# main.net
KiCad netlist of a schematic drawn in Altium Designer
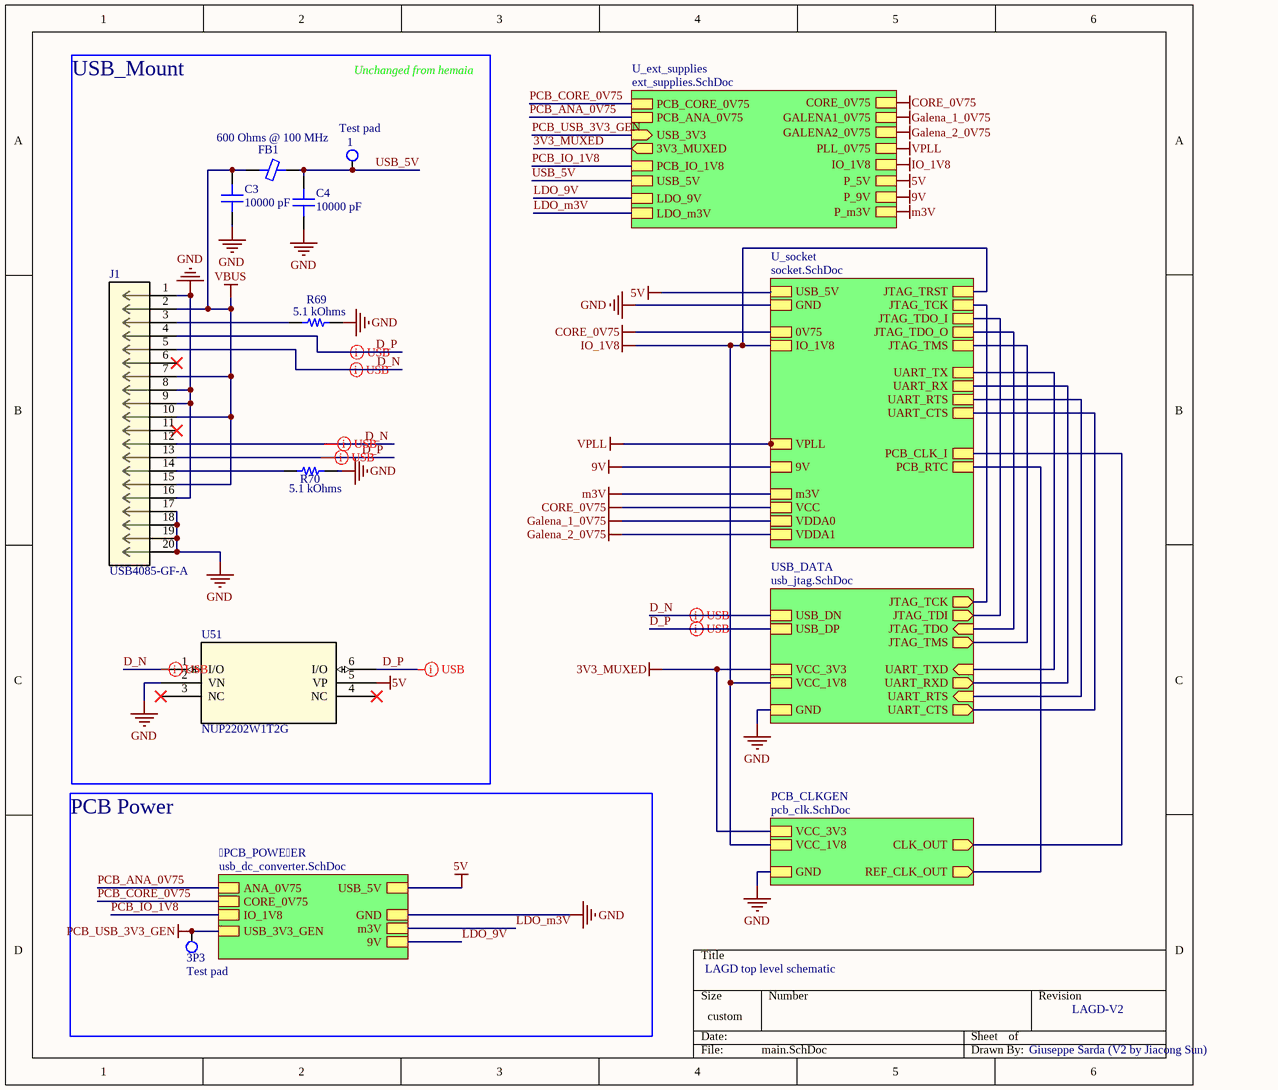
[diagram p0: main.SchDoc]

(export (version "E")
  (design (tool "Eeschema 10.0.6"))
  (components
    (comp (ref "1") (value "Test pad") (footprint "Test Pad") (libsource (lib "Hemaia") (part "Test pad")))
    (comp (ref "3P3") (value "Test pad") (footprint "Test Pad") (libsource (lib "Hemaia") (part "Test pad")))
    (comp (ref "C3")
      (value "10000 pF")
      (footprint "CAP 0805_2012")
      (description "CAP CER 0805 10NF 25V C0G 1%")
      (fields
        (field (name "PART NUMBER") "C0805C103F3GECTU")
        (field (name "CAPACITANCE") "10000 pF")
        (field (name "MANUFACTURER") "KEMET")
      )
      (libsource (lib "Celestial Altium Library - altium_library") (part "Capacitor"))
    )
    (comp (ref "C4")
      (value "10000 pF")
      (footprint "CAP 0805_2012")
      (description "CAP CER 0805 10NF 25V C0G 1%")
      (fields
        (field (name "PART NUMBER") "C0805C103F3GECTU")
        (field (name "CAPACITANCE") "10000 pF")
        (field (name "MANUFACTURER") "KEMET")
      )
      (libsource (lib "Celestial Altium Library - altium_library") (part "Capacitor"))
    )
    (comp (ref "FB1")
      (value "600 Ohms @ 100 MHz")
      (footprint "FER 0805_2012")
      (description "FERRITE BEAD 600 OHM 0805 1LN")
      (fields
        (field (name "PART NUMBER") "BLM21HE601SH1L")
        (field (name "MANUFACTURER") "Murata Electronics")
      )
      (libsource (lib "Celestial Altium Library - altium_library") (part "Ferrite Chip"))
    )
    (comp (ref "J1")
      (value "USB4085-GF-A")
      (footprint "FP-USB4085-GF-A-MFG")
      (description "Description")
      (fields (field (name "COPYRIGHT") "Copyright (C) 2025 Ultra Librarian. All rights reserved."))
      (libsource (lib "Connectors") (part "USB4085-GF-A"))
    )
    (comp (ref "R69")
      (value "5.1 kOhms")
      (footprint "RES 0805_2012")
      (description "RES 5.1K OHM 5% 1/4W 0805")
      (fields (field (name "PART NUMBER") "560112120019") (field (name "MANUFACTURER") "Würth Elektronik"))
      (libsource (lib "Celestial Altium Library - altium_library") (part "Resistor"))
    )
    (comp (ref "R70")
      (value "5.1 kOhms")
      (footprint "RES 0805_2012")
      (description "RES 5.1K OHM 5% 1/4W 0805")
      (fields (field (name "PART NUMBER") "560112120019") (field (name "MANUFACTURER") "Würth Elektronik"))
      (libsource (lib "Celestial Altium Library - altium_library") (part "Resistor"))
    )
    (comp (ref "U51")
      (value "NUP2202W1T2G")
      (footprint "SOT-363-6_2P2X1P35_ONS")
      (description "Description")
      (fields (field (name "COPYRIGHT") "Copyright (C) 2025 Ultra Librarian. All rights reserved."))
      (libsource (lib "Diodes") (part "NUP2202W1T2G"))
    )
  )
  (nets
    (net (code "2") (name "/D_N") (class "Default")
      (node (ref "J1") (pin "12") (pinfunction "12_12") (pintype "passive"))
      (node (ref "J1") (pin "5") (pinfunction "5_5") (pintype "passive"))
      (node (ref "U51") (pin "1") (pinfunction "I/O_1") (pintype "bidirectional"))
    )
    (net (code "3") (name "/D_P") (class "Default")
      (node (ref "J1") (pin "13") (pinfunction "13_13") (pintype "passive"))
      (node (ref "J1") (pin "4") (pinfunction "4_4") (pintype "passive"))
      (node (ref "U51") (pin "6") (pinfunction "I/O_6") (pintype "bidirectional"))
    )
    (net (code "18") (name "/USB_5V") (class "Default")
      (node (ref "1") (pin "1") (pintype "passive"))
      (node (ref "C4") (pin "1") (pinfunction "1_1") (pintype "passive"))
      (node (ref "FB1") (pin "2") (pinfunction "2_2") (pintype "passive"))
    )
    (net (code "20") (name "5V") (class "Default")
      (node (ref "U51") (pin "5") (pinfunction "VP_5") (pintype "power_in"))
    )
    (net (code "23") (name "GND") (class "Default")
      (node (ref "C3") (pin "2") (pinfunction "2_2") (pintype "passive"))
      (node (ref "C4") (pin "2") (pinfunction "2_2") (pintype "passive"))
      (node (ref "J1") (pin "1") (pinfunction "1_1") (pintype "passive"))
      (node (ref "J1") (pin "16") (pinfunction "16_16") (pintype "passive"))
      (node (ref "J1") (pin "17") (pinfunction "17_17") (pintype "passive"))
      (node (ref "J1") (pin "18") (pinfunction "18_18") (pintype "passive"))
      (node (ref "J1") (pin "19") (pinfunction "19_19") (pintype "passive"))
      (node (ref "J1") (pin "20") (pinfunction "20_20") (pintype "passive"))
      (node (ref "J1") (pin "8") (pinfunction "8_8") (pintype "passive"))
      (node (ref "J1") (pin "9") (pinfunction "9_9") (pintype "passive"))
      (node (ref "R69") (pin "2") (pinfunction "2_2") (pintype "passive"))
      (node (ref "R70") (pin "2") (pinfunction "2_2") (pintype "passive"))
      (node (ref "U51") (pin "2") (pinfunction "VN_2") (pintype "power_in"))
    )
    (net (code "27") (name "Net-(J1-Pad3)") (class "Default")
      (node (ref "J1") (pin "3") (pinfunction "3_3") (pintype "passive"))
      (node (ref "R69") (pin "1") (pinfunction "1_1") (pintype "passive"))
    )
    (net (code "28") (name "Net-(J1-Pad14)") (class "Default")
      (node (ref "J1") (pin "14") (pinfunction "14_14") (pintype "passive"))
      (node (ref "R70") (pin "1") (pinfunction "1_1") (pintype "passive"))
    )
    (net (code "29") (name "PCB_USB_3V3_GEN") (class "Default")
      (node (ref "3P3") (pin "1") (pintype "passive"))
    )
    (net (code "30") (name "VBUS") (class "Default")
      (node (ref "C3") (pin "1") (pinfunction "1_1") (pintype "passive"))
      (node (ref "FB1") (pin "1") (pinfunction "1_1") (pintype "passive"))
      (node (ref "J1") (pin "10") (pinfunction "10_10") (pintype "passive"))
      (node (ref "J1") (pin "15") (pinfunction "15_15") (pintype "passive"))
      (node (ref "J1") (pin "2") (pinfunction "2_2") (pintype "passive"))
      (node (ref "J1") (pin "7") (pinfunction "7_7") (pintype "passive"))
    )
    (net (code "33") (name "unconnected-(J1-Pad6)") (class "Default")
      (node (ref "J1") (pin "6") (pinfunction "6_6") (pintype "passive+no_connect"))
    )
    (net (code "34") (name "unconnected-(J1-Pad11)") (class "Default")
      (node (ref "J1") (pin "11") (pinfunction "11_11") (pintype "passive+no_connect"))
    )
    (net (code "35") (name "unconnected-(U51-NC-Pad3)") (class "Default")
      (node (ref "U51") (pin "3") (pinfunction "NC_3") (pintype "passive+no_connect"))
    )
    (net (code "36") (name "unconnected-(U51-NC-Pad4)") (class "Default")
      (node (ref "U51") (pin "4") (pinfunction "NC_4") (pintype "passive+no_connect"))
    )
  )
)
